# 02_STEPPERS.net
KiCad netlist of a schematic drawn in Altium Designer
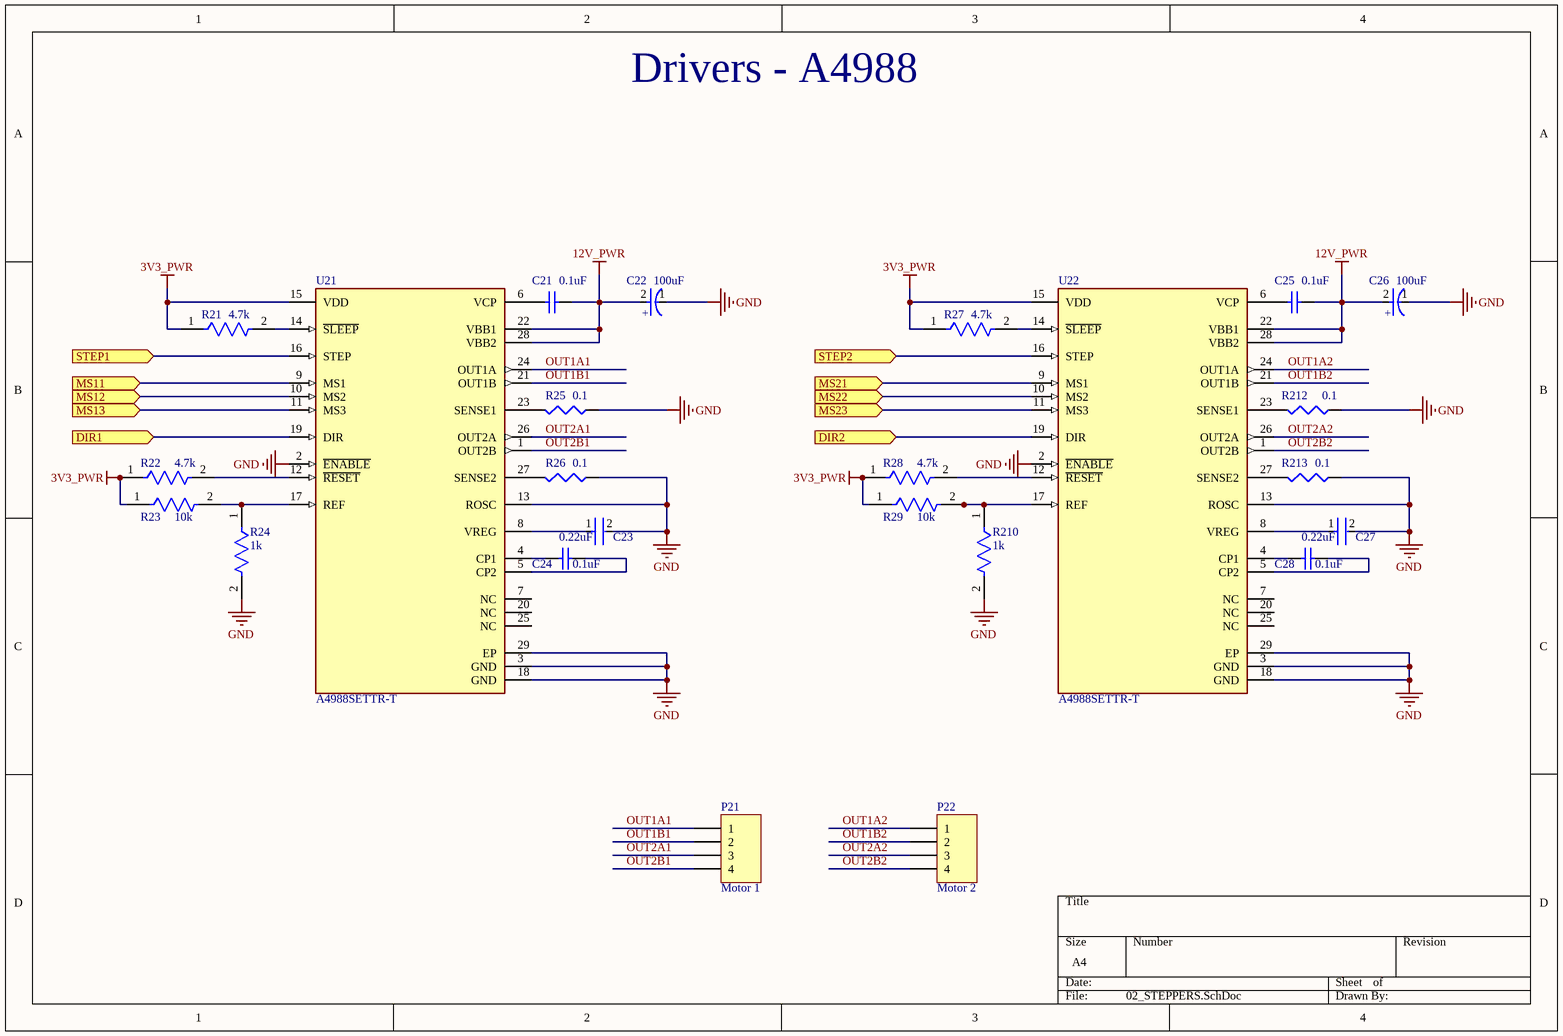
[diagram p0: 02_STEPPERS.SchDoc]

(export (version "E")
  (design (tool "Eeschema 10.0.6"))
  (components
    (comp (ref "C21")
      (value "0.1uF")
      (footprint "CAPC1608X90X35ML15T15")
      (fields
        (field (name "PART NUMBER") "06033C104KAT4A")
        (field (name "MANUFACTURER") "AVX Interconnect / Elco")
        (field (name "TOLERANCE") "10%")
      )
      (libsource (lib "Altium Content Vault") (part "CAP"))
    )
    (comp (ref "C22")
      (value "100uF")
      (footprint "FP-MAL2150-1010-MFG")
      (description "CAP ALUM 100UF 20% 50V SMD")
      (fields (field (name "TOLERANCE") "20%") (field (name "MANUFACTURER") "Vishay BCcomponents"))
      (libsource (lib "Altium Content Vault") (part "203bc49f2ac43e59fd269a8c329ed05"))
    )
    (comp (ref "C23")
      (value "0.22uF")
      (footprint "FP-GCM188-0_1-IPC_B")
      (description "Ceramic Capacitor for Automotive 220nF  ±10% 25VDC X7R 0603 Paper T/R")
      (fields (field (name "TOLERANCE") "10%") (field (name "MANUFACTURER") "Murata"))
      (libsource (lib "Altium Content Vault") (part "02cd4be3c70576c341d710602a673aa"))
    )
    (comp (ref "C24")
      (value "0.1uF")
      (footprint "CAPC1608X90X35ML15T15")
      (fields
        (field (name "PART NUMBER") "06033C104KAT4A")
        (field (name "MANUFACTURER") "AVX Interconnect / Elco")
        (field (name "TOLERANCE") "10%")
      )
      (libsource (lib "Altium Content Vault") (part "CAP"))
    )
    (comp (ref "C25")
      (value "0.1uF")
      (footprint "CAPC1608X90X35ML15T15")
      (fields
        (field (name "PART NUMBER") "06033C104KAT4A")
        (field (name "MANUFACTURER") "AVX Interconnect / Elco")
        (field (name "TOLERANCE") "10%")
      )
      (libsource (lib "Altium Content Vault") (part "CAP"))
    )
    (comp (ref "C26")
      (value "100uF")
      (footprint "FP-MAL2150-1010-MFG")
      (description "CAP ALUM 100UF 20% 50V SMD")
      (fields (field (name "TOLERANCE") "20%") (field (name "MANUFACTURER") "Vishay BCcomponents"))
      (libsource (lib "Altium Content Vault") (part "203bc49f2ac43e59fd269a8c329ed05"))
    )
    (comp (ref "C27")
      (value "0.22uF")
      (footprint "FP-GCM188-0_1-IPC_B")
      (description "Ceramic Capacitor for Automotive 220nF  ±10% 25VDC X7R 0603 Paper T/R")
      (fields (field (name "TOLERANCE") "10%") (field (name "MANUFACTURER") "Murata"))
      (libsource (lib "Altium Content Vault") (part "02cd4be3c70576c341d710602a673aa"))
    )
    (comp (ref "C28")
      (value "0.1uF")
      (footprint "CAPC1608X90X35ML15T15")
      (fields
        (field (name "PART NUMBER") "06033C104KAT4A")
        (field (name "MANUFACTURER") "AVX Interconnect / Elco")
        (field (name "TOLERANCE") "10%")
      )
      (libsource (lib "Altium Content Vault") (part "CAP"))
    )
    (comp (ref "P21")
      (value "Motor 1")
      (footprint "HDR1X4")
      (description "Header, 4-Pin")
      (fields (field (name "PUBLISHER") "Altium Limited"))
      (libsource (lib "Miscellaneous Connectors") (part "Header 4"))
    )
    (comp (ref "P22")
      (value "Motor 2")
      (footprint "HDR1X4")
      (description "Header, 4-Pin")
      (fields (field (name "PUBLISHER") "Altium Limited"))
      (libsource (lib "Miscellaneous Connectors") (part "Header 4"))
    )
    (comp (ref "R21")
      (value "4.7k")
      (footprint "FP-MCT0603-IPC_B")
      (description "RES SMD 100 OHM 1% 1/8W 0603")
      (fields (field (name "TOLERANCE") "0.1%") (field (name "MANUFACTURER") "Vishay BCcomponents"))
      (libsource (lib "Altium Content Vault") (part "1029c3af85768c4190bb7ad29bc67b5"))
    )
    (comp (ref "R22")
      (value "4.7k")
      (footprint "FP-MCT0603-IPC_B")
      (description "RES SMD 100 OHM 1% 1/8W 0603")
      (fields (field (name "TOLERANCE") "0.1%") (field (name "MANUFACTURER") "Vishay BCcomponents"))
      (libsource (lib "Altium Content Vault") (part "1029c3af85768c4190bb7ad29bc67b5"))
    )
    (comp (ref "R23")
      (value "10k")
      (footprint "FP-AC0603-MFG")
      (description "RES 10KΩ 1.00% 0.1W 0603")
      (fields (field (name "TOLERANCE") "1%") (field (name "MANUFACTURER") "Yageo"))
      (libsource (lib "Altium Content Vault") (part "1029c3af85768c4190bb7ad29bc67b5"))
    )
    (comp (ref "R24")
      (value "1k")
      (footprint "FP-RC0603-0_55-IPC_C")
      (description "RES 1K OHM 1% 1/10W 0603")
      (fields (field (name "TOLERANCE") "1%") (field (name "MANUFACTURER") "Yageo"))
      (libsource (lib "Altium Content Vault") (part "1029c3af85768c4190bb7ad29bc67b5"))
    )
    (comp (ref "R25")
      (value "0.1")
      (footprint "J1-0603")
      (description "Thick Film Surface Mount Chip Resistor 0603 Size 0.1 Ohm 5% 0.1 W ±400 ppm/°C 2-Pin SMD T/R")
      (fields
        (field (name "MANUFACTURER") "Vishay Dale")
        (field (name "MANUFACTURER PART NUMBER") "RCWL0603R100JQEA")
        (field (name "PUBLISHER") "Altium Limited")
      )
      (libsource (lib "Miscellaneous Devices") (part "Res3"))
    )
    (comp (ref "R26")
      (value "0.1")
      (footprint "J1-0603")
      (description "Thick Film Surface Mount Chip Resistor 0603 Size 0.1 Ohm 5% 0.1 W ±400 ppm/°C 2-Pin SMD T/R")
      (fields
        (field (name "MANUFACTURER") "Vishay Dale")
        (field (name "MANUFACTURER PART NUMBER") "RCWL0603R100JQEA")
        (field (name "PUBLISHER") "Altium Limited")
      )
      (libsource (lib "Miscellaneous Devices") (part "Res3"))
    )
    (comp (ref "R27")
      (value "4.7k")
      (footprint "FP-MCT0603-IPC_B")
      (description "RES SMD 100 OHM 1% 1/8W 0603")
      (fields (field (name "TOLERANCE") "0.1%") (field (name "MANUFACTURER") "Vishay BCcomponents"))
      (libsource (lib "Altium Content Vault") (part "1029c3af85768c4190bb7ad29bc67b5"))
    )
    (comp (ref "R28")
      (value "4.7k")
      (footprint "FP-MCT0603-IPC_B")
      (description "RES SMD 100 OHM 1% 1/8W 0603")
      (fields (field (name "TOLERANCE") "0.1%") (field (name "MANUFACTURER") "Vishay BCcomponents"))
      (libsource (lib "Altium Content Vault") (part "1029c3af85768c4190bb7ad29bc67b5"))
    )
    (comp (ref "R29")
      (value "10k")
      (footprint "FP-AC0603-MFG")
      (description "RES 10KΩ 1.00% 0.1W 0603")
      (fields (field (name "TOLERANCE") "1%") (field (name "MANUFACTURER") "Yageo"))
      (libsource (lib "Altium Content Vault") (part "1029c3af85768c4190bb7ad29bc67b5"))
    )
    (comp (ref "R210")
      (value "1k")
      (footprint "FP-RC0603-0_55-IPC_C")
      (description "RES 1K OHM 1% 1/10W 0603")
      (fields (field (name "TOLERANCE") "1%") (field (name "MANUFACTURER") "Yageo"))
      (libsource (lib "Altium Content Vault") (part "1029c3af85768c4190bb7ad29bc67b5"))
    )
    (comp (ref "R212")
      (value "0.1")
      (footprint "J1-0603")
      (description "Thick Film Surface Mount Chip Resistor 0603 Size 0.1 Ohm 5% 0.1 W ±400 ppm/°C 2-Pin SMD T/R")
      (fields
        (field (name "MANUFACTURER") "Vishay Dale")
        (field (name "MANUFACTURER PART NUMBER") "RCWL0603R100JQEA")
        (field (name "PUBLISHER") "Altium Limited")
      )
      (libsource (lib "Miscellaneous Devices") (part "Res3"))
    )
    (comp (ref "R213")
      (value "0.1")
      (footprint "J1-0603")
      (description "Thick Film Surface Mount Chip Resistor 0603 Size 0.1 Ohm 5% 0.1 W ±400 ppm/°C 2-Pin SMD T/R")
      (fields
        (field (name "MANUFACTURER") "Vishay Dale")
        (field (name "MANUFACTURER PART NUMBER") "RCWL0603R100JQEA")
        (field (name "PUBLISHER") "Altium Limited")
      )
      (libsource (lib "Miscellaneous Devices") (part "Res3"))
    )
    (comp (ref "U21")
      (value "A4988SETTR-T")
      (footprint "FP-ET-28-MFG")
      (description "IC MTR DRVR BIPOLAR 3-5.5V 28QFN")
      (fields (field (name "MANUFACTURER") "Allegro MicroSystems"))
      (libsource (lib "Altium Content Vault") (part "7d8f66b9ff4f6e67aa26ce86ffb8e2d"))
    )
    (comp (ref "U22")
      (value "A4988SETTR-T")
      (footprint "FP-ET-28-MFG")
      (description "IC MTR DRVR BIPOLAR 3-5.5V 28QFN")
      (fields (field (name "MANUFACTURER") "Allegro MicroSystems"))
      (libsource (lib "Altium Content Vault") (part "7d8f66b9ff4f6e67aa26ce86ffb8e2d"))
    )
  )
  (nets
    (net (code "1") (name "/DIR1") (class "Default")
      (node (ref "U21") (pin "19") (pinfunction "DIR_19") (pintype "input"))
    )
    (net (code "2") (name "/DIR2") (class "Default")
      (node (ref "U22") (pin "19") (pinfunction "DIR_19") (pintype "input"))
    )
    (net (code "3") (name "/MS11") (class "Default")
      (node (ref "U21") (pin "9") (pinfunction "MS1_9") (pintype "input"))
    )
    (net (code "4") (name "/MS12") (class "Default")
      (node (ref "U21") (pin "10") (pinfunction "MS2_10") (pintype "input"))
    )
    (net (code "5") (name "/MS13") (class "Default")
      (node (ref "U21") (pin "11") (pinfunction "MS3_11") (pintype "input"))
    )
    (net (code "6") (name "/MS21") (class "Default")
      (node (ref "U22") (pin "9") (pinfunction "MS1_9") (pintype "input"))
    )
    (net (code "7") (name "/MS22") (class "Default")
      (node (ref "U22") (pin "10") (pinfunction "MS2_10") (pintype "input"))
    )
    (net (code "8") (name "/MS23") (class "Default")
      (node (ref "U22") (pin "11") (pinfunction "MS3_11") (pintype "input"))
    )
    (net (code "9") (name "/OUT1A1") (class "Default")
      (node (ref "P21") (pin "1") (pinfunction "1_1") (pintype "passive"))
      (node (ref "U21") (pin "24") (pinfunction "OUT1A_24") (pintype "output"))
    )
    (net (code "10") (name "/OUT1A2") (class "Default")
      (node (ref "P22") (pin "1") (pinfunction "1_1") (pintype "passive"))
      (node (ref "U22") (pin "24") (pinfunction "OUT1A_24") (pintype "output"))
    )
    (net (code "11") (name "/OUT1B1") (class "Default")
      (node (ref "P21") (pin "2") (pinfunction "2_2") (pintype "passive"))
      (node (ref "U21") (pin "21") (pinfunction "OUT1B_21") (pintype "output"))
    )
    (net (code "12") (name "/OUT1B2") (class "Default")
      (node (ref "P22") (pin "2") (pinfunction "2_2") (pintype "passive"))
      (node (ref "U22") (pin "21") (pinfunction "OUT1B_21") (pintype "output"))
    )
    (net (code "13") (name "/OUT2A1") (class "Default")
      (node (ref "P21") (pin "3") (pinfunction "3_3") (pintype "passive"))
      (node (ref "U21") (pin "26") (pinfunction "OUT2A_26") (pintype "output"))
    )
    (net (code "14") (name "/OUT2A2") (class "Default")
      (node (ref "P22") (pin "3") (pinfunction "3_3") (pintype "passive"))
      (node (ref "U22") (pin "26") (pinfunction "OUT2A_26") (pintype "output"))
    )
    (net (code "15") (name "/OUT2B1") (class "Default")
      (node (ref "P21") (pin "4") (pinfunction "4_4") (pintype "passive"))
      (node (ref "U21") (pin "1") (pinfunction "OUT2B_1") (pintype "output"))
    )
    (net (code "16") (name "/OUT2B2") (class "Default")
      (node (ref "P22") (pin "4") (pinfunction "4_4") (pintype "passive"))
      (node (ref "U22") (pin "1") (pinfunction "OUT2B_1") (pintype "output"))
    )
    (net (code "17") (name "/STEP1") (class "Default")
      (node (ref "U21") (pin "16") (pinfunction "STEP_16") (pintype "input"))
    )
    (net (code "18") (name "/STEP2") (class "Default")
      (node (ref "U22") (pin "16") (pinfunction "STEP_16") (pintype "input"))
    )
    (net (code "19") (name "3V3_PWR") (class "Default")
      (node (ref "R21") (pin "1") (pinfunction "1_1") (pintype "passive"))
      (node (ref "R22") (pin "1") (pinfunction "1_1") (pintype "passive"))
      (node (ref "R23") (pin "1") (pinfunction "1_1") (pintype "passive"))
      (node (ref "R27") (pin "1") (pinfunction "1_1") (pintype "passive"))
      (node (ref "R28") (pin "1") (pinfunction "1_1") (pintype "passive"))
      (node (ref "R29") (pin "1") (pinfunction "1_1") (pintype "passive"))
      (node (ref "U21") (pin "15") (pinfunction "VDD_15") (pintype "power_in"))
      (node (ref "U22") (pin "15") (pinfunction "VDD_15") (pintype "power_in"))
    )
    (net (code "20") (name "12V_PWR") (class "Default")
      (node (ref "C21") (pin "2") (pinfunction "2_2") (pintype "passive"))
      (node (ref "C22") (pin "2") (pinfunction "A_2") (pintype "passive"))
      (node (ref "C25") (pin "2") (pinfunction "2_2") (pintype "passive"))
      (node (ref "C26") (pin "2") (pinfunction "A_2") (pintype "passive"))
      (node (ref "U21") (pin "22") (pinfunction "VBB1_22") (pintype "power_in"))
      (node (ref "U21") (pin "28") (pinfunction "VBB2_28") (pintype "power_in"))
      (node (ref "U22") (pin "22") (pinfunction "VBB1_22") (pintype "power_in"))
      (node (ref "U22") (pin "28") (pinfunction "VBB2_28") (pintype "power_in"))
    )
    (net (code "21") (name "GND") (class "Default")
      (node (ref "C22") (pin "1") (pinfunction "C_1") (pintype "passive"))
      (node (ref "C23") (pin "2") (pinfunction "2_2") (pintype "passive"))
      (node (ref "C26") (pin "1") (pinfunction "C_1") (pintype "passive"))
      (node (ref "C27") (pin "2") (pinfunction "2_2") (pintype "passive"))
      (node (ref "R210") (pin "2") (pinfunction "2_2") (pintype "passive"))
      (node (ref "R212") (pin "1") (pinfunction "1_1") (pintype "passive"))
      (node (ref "R213") (pin "1") (pinfunction "1_1") (pintype "passive"))
      (node (ref "R24") (pin "2") (pinfunction "2_2") (pintype "passive"))
      (node (ref "R25") (pin "1") (pinfunction "1_1") (pintype "passive"))
      (node (ref "R26") (pin "1") (pinfunction "1_1") (pintype "passive"))
      (node (ref "U21") (pin "13") (pinfunction "ROSC_13") (pintype "passive"))
      (node (ref "U21") (pin "18") (pinfunction "GND_18") (pintype "power_in"))
      (node (ref "U21") (pin "2") (pinfunction "~{ENABLE}_2") (pintype "input"))
      (node (ref "U21") (pin "29") (pinfunction "EP_29") (pintype "power_in"))
      (node (ref "U21") (pin "3") (pinfunction "GND_3") (pintype "power_in"))
      (node (ref "U22") (pin "13") (pinfunction "ROSC_13") (pintype "passive"))
      (node (ref "U22") (pin "18") (pinfunction "GND_18") (pintype "power_in"))
      (node (ref "U22") (pin "2") (pinfunction "~{ENABLE}_2") (pintype "input"))
      (node (ref "U22") (pin "29") (pinfunction "EP_29") (pintype "power_in"))
      (node (ref "U22") (pin "3") (pinfunction "GND_3") (pintype "power_in"))
    )
    (net (code "22") (name "Net-(U21-CP1)") (class "Default")
      (node (ref "C24") (pin "2") (pinfunction "2_2") (pintype "passive"))
      (node (ref "U21") (pin "4") (pinfunction "CP1_4") (pintype "passive"))
    )
    (net (code "23") (name "Net-(U21-CP2)") (class "Default")
      (node (ref "C24") (pin "1") (pinfunction "1_1") (pintype "passive"))
      (node (ref "U21") (pin "5") (pinfunction "CP2_5") (pintype "passive"))
    )
    (net (code "24") (name "Net-(U21-REF)") (class "Default")
      (node (ref "R23") (pin "2") (pinfunction "2_2") (pintype "passive"))
      (node (ref "R24") (pin "1") (pinfunction "1_1") (pintype "passive"))
      (node (ref "U21") (pin "17") (pinfunction "REF_17") (pintype "input"))
    )
    (net (code "25") (name "Net-(U21-SENSE1)") (class "Default")
      (node (ref "R25") (pin "2") (pinfunction "2_2") (pintype "passive"))
      (node (ref "U21") (pin "23") (pinfunction "SENSE1_23") (pintype "passive"))
    )
    (net (code "26") (name "Net-(U21-SENSE2)") (class "Default")
      (node (ref "R26") (pin "2") (pinfunction "2_2") (pintype "passive"))
      (node (ref "U21") (pin "27") (pinfunction "SENSE2_27") (pintype "passive"))
    )
    (net (code "27") (name "Net-(U21-VCP)") (class "Default")
      (node (ref "C21") (pin "1") (pinfunction "1_1") (pintype "passive"))
      (node (ref "U21") (pin "6") (pinfunction "VCP_6") (pintype "passive"))
    )
    (net (code "28") (name "Net-(U21-VREG)") (class "Default")
      (node (ref "C23") (pin "1") (pinfunction "1_1") (pintype "passive"))
      (node (ref "U21") (pin "8") (pinfunction "VREG_8") (pintype "passive"))
    )
    (net (code "29") (name "Net-(U21-~{RESET})") (class "Default")
      (node (ref "R22") (pin "2") (pinfunction "2_2") (pintype "passive"))
      (node (ref "U21") (pin "12") (pinfunction "~{RESET}_12") (pintype "input"))
    )
    (net (code "30") (name "Net-(U21-~{SLEEP})") (class "Default")
      (node (ref "R21") (pin "2") (pinfunction "2_2") (pintype "passive"))
      (node (ref "U21") (pin "14") (pinfunction "~{SLEEP}_14") (pintype "input"))
    )
    (net (code "31") (name "Net-(U22-CP1)") (class "Default")
      (node (ref "C28") (pin "2") (pinfunction "2_2") (pintype "passive"))
      (node (ref "U22") (pin "4") (pinfunction "CP1_4") (pintype "passive"))
    )
    (net (code "32") (name "Net-(U22-CP2)") (class "Default")
      (node (ref "C28") (pin "1") (pinfunction "1_1") (pintype "passive"))
      (node (ref "U22") (pin "5") (pinfunction "CP2_5") (pintype "passive"))
    )
    (net (code "33") (name "Net-(U22-REF)") (class "Default")
      (node (ref "R210") (pin "1") (pinfunction "1_1") (pintype "passive"))
      (node (ref "R29") (pin "2") (pinfunction "2_2") (pintype "passive"))
      (node (ref "U22") (pin "17") (pinfunction "REF_17") (pintype "input"))
    )
    (net (code "34") (name "Net-(U22-SENSE1)") (class "Default")
      (node (ref "R212") (pin "2") (pinfunction "2_2") (pintype "passive"))
      (node (ref "U22") (pin "23") (pinfunction "SENSE1_23") (pintype "passive"))
    )
    (net (code "35") (name "Net-(U22-SENSE2)") (class "Default")
      (node (ref "R213") (pin "2") (pinfunction "2_2") (pintype "passive"))
      (node (ref "U22") (pin "27") (pinfunction "SENSE2_27") (pintype "passive"))
    )
    (net (code "36") (name "Net-(U22-VCP)") (class "Default")
      (node (ref "C25") (pin "1") (pinfunction "1_1") (pintype "passive"))
      (node (ref "U22") (pin "6") (pinfunction "VCP_6") (pintype "passive"))
    )
    (net (code "37") (name "Net-(U22-VREG)") (class "Default")
      (node (ref "C27") (pin "1") (pinfunction "1_1") (pintype "passive"))
      (node (ref "U22") (pin "8") (pinfunction "VREG_8") (pintype "passive"))
    )
    (net (code "38") (name "Net-(U22-~{RESET})") (class "Default")
      (node (ref "R28") (pin "2") (pinfunction "2_2") (pintype "passive"))
      (node (ref "U22") (pin "12") (pinfunction "~{RESET}_12") (pintype "input"))
    )
    (net (code "39") (name "Net-(U22-~{SLEEP})") (class "Default")
      (node (ref "R27") (pin "2") (pinfunction "2_2") (pintype "passive"))
      (node (ref "U22") (pin "14") (pinfunction "~{SLEEP}_14") (pintype "input"))
    )
    (net (code "40") (name "unconnected-(U21-NC-Pad7)") (class "Default")
      (node (ref "U21") (pin "7") (pinfunction "NC_7") (pintype "passive"))
    )
    (net (code "41") (name "unconnected-(U21-NC-Pad20)") (class "Default")
      (node (ref "U21") (pin "20") (pinfunction "NC_20") (pintype "passive"))
    )
    (net (code "42") (name "unconnected-(U21-NC-Pad25)") (class "Default")
      (node (ref "U21") (pin "25") (pinfunction "NC_25") (pintype "passive"))
    )
    (net (code "43") (name "unconnected-(U22-NC-Pad7)") (class "Default")
      (node (ref "U22") (pin "7") (pinfunction "NC_7") (pintype "passive"))
    )
    (net (code "44") (name "unconnected-(U22-NC-Pad20)") (class "Default")
      (node (ref "U22") (pin "20") (pinfunction "NC_20") (pintype "passive"))
    )
    (net (code "45") (name "unconnected-(U22-NC-Pad25)") (class "Default")
      (node (ref "U22") (pin "25") (pinfunction "NC_25") (pintype "passive"))
    )
  )
)
